# CC3000_Breakout.net
KiCad netlist of a schematic drawn in EAGLE
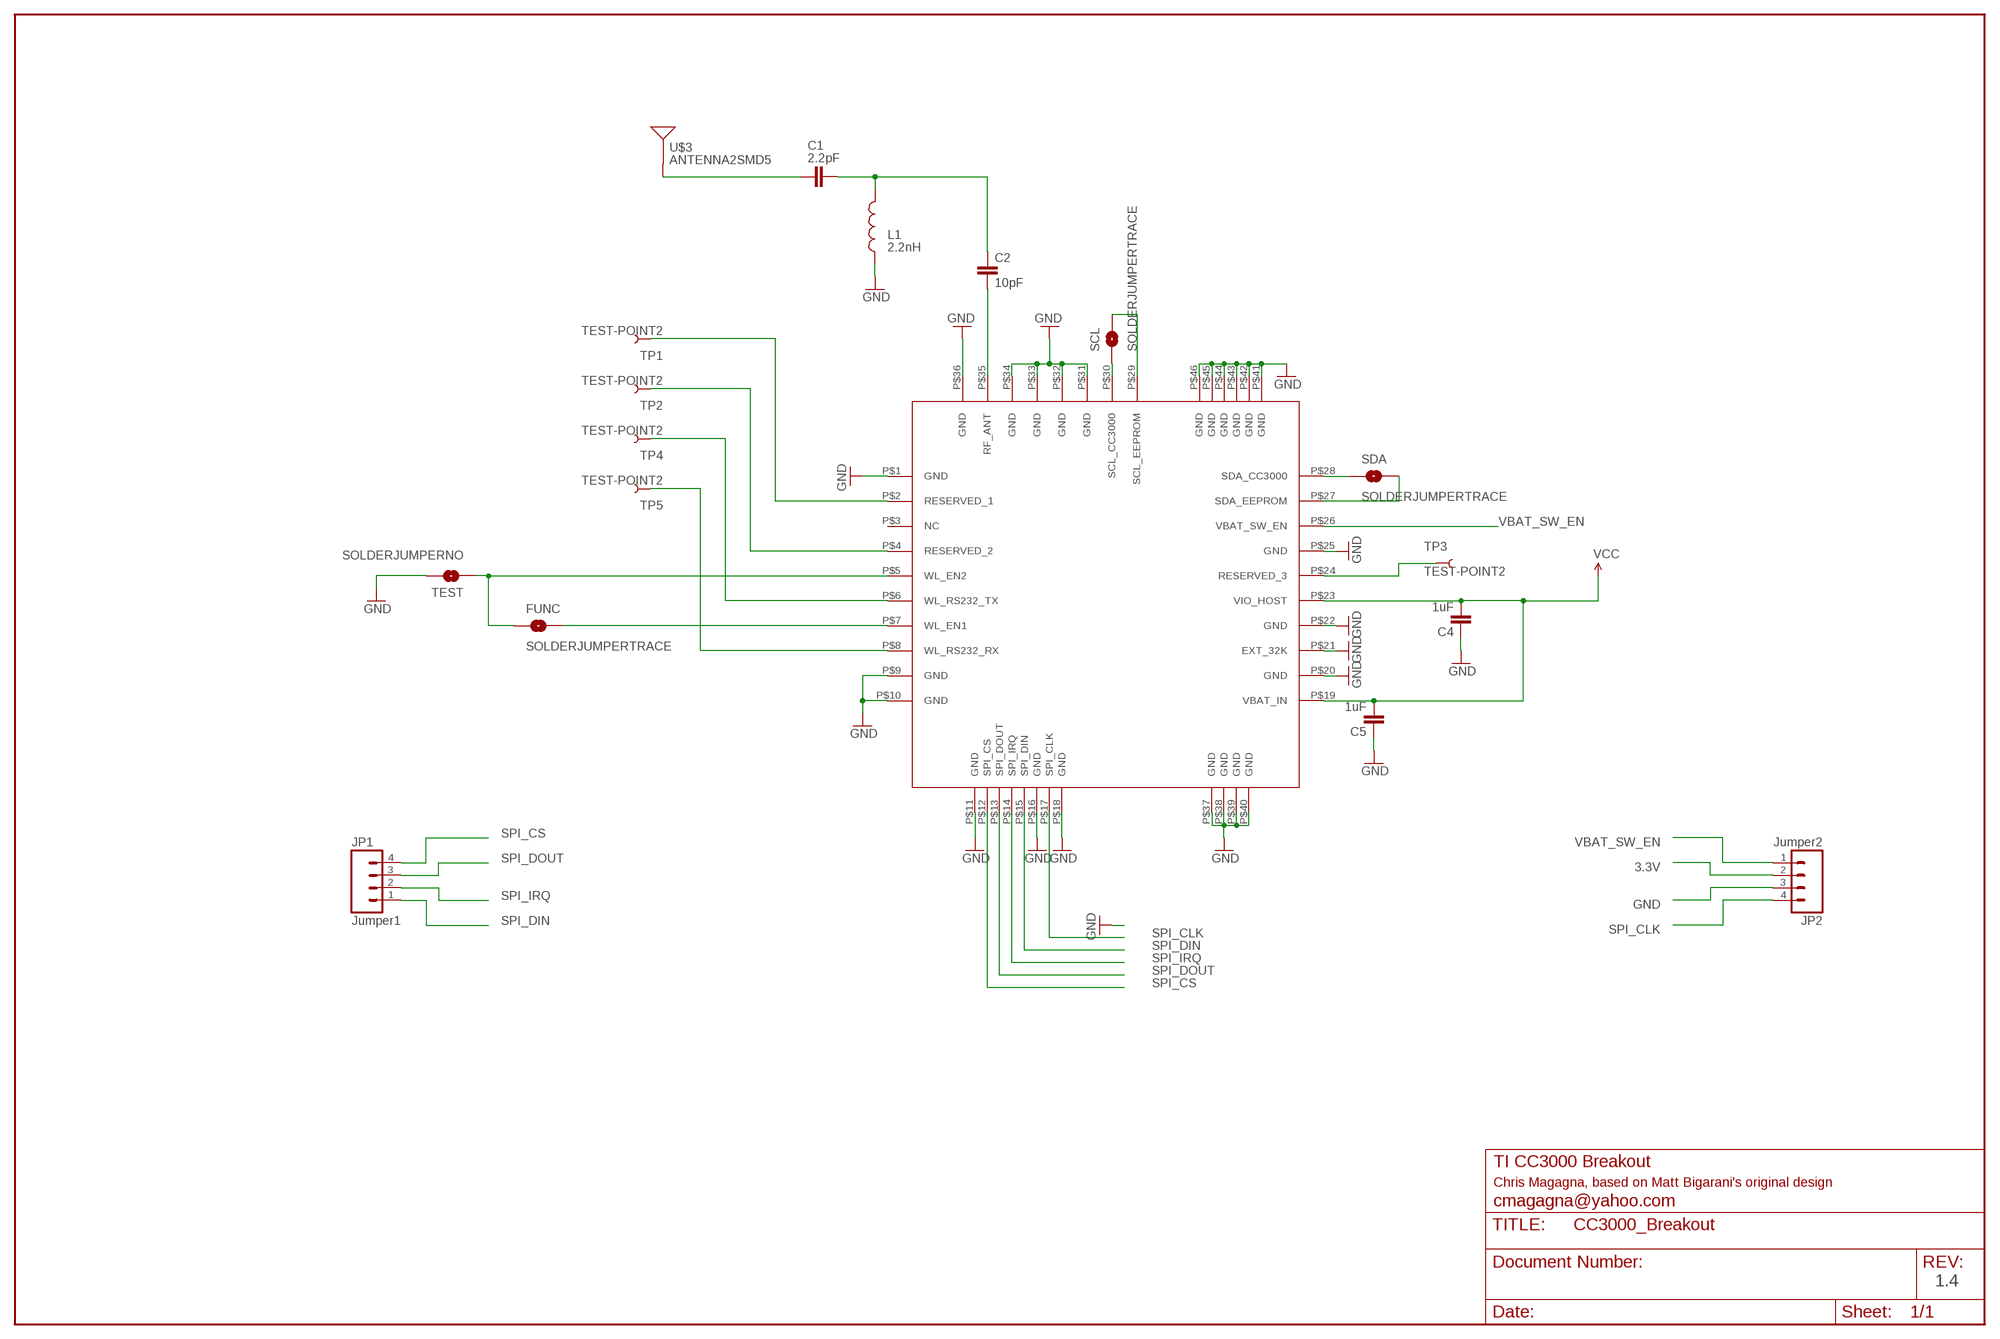
[diagram p0: schematic, sheet 1]

(export (version "E")
  (design (tool "Eeschema 10.0.6"))
  (components
    (comp (ref "C1")
      (value "2.2pF")
      (footprint "eagle-import:0402-CAP")
      (libsource (lib "eagle-import") (part "CAP0402-CAP"))
    )
    (comp (ref "C2")
      (value "10pF")
      (footprint "eagle-import:0402-CAP")
      (libsource (lib "eagle-import") (part "CAP0402-CAP"))
    )
    (comp (ref "C4")
      (value "1uF")
      (footprint "eagle-import:0402-CAP")
      (libsource (lib "eagle-import") (part "CAP0402-CAP"))
    )
    (comp (ref "C5")
      (value "1uF")
      (footprint "eagle-import:0402-CAP")
      (libsource (lib "eagle-import") (part "CAP0402-CAP"))
    )
    (comp (ref "FUNC")
      (value "SOLDERJUMPERTRACE")
      (footprint "eagle-import:SJ_2S-TRACE")
      (libsource (lib "eagle-import") (part "SparkFun-Passives_SOLDERJUMPERTRACE"))
    )
    (comp (ref "JP1")
      (value "Jumper1")
      (footprint "eagle-import:1X04")
      (libsource (lib "eagle-import") (part "M04PTH"))
    )
    (comp (ref "JP2")
      (value "Jumper2")
      (footprint "eagle-import:1X04")
      (libsource (lib "eagle-import") (part "M04PTH"))
    )
    (comp (ref "L1")
      (value "2.2nH")
      (footprint "eagle-import:C0402")
      (libsource (lib "eagle-import") (part "INDUCTOR0402"))
    )
    (comp (ref "SCL")
      (value "SOLDERJUMPERTRACE")
      (footprint "eagle-import:SJ_2S-TRACE")
      (libsource (lib "eagle-import") (part "SparkFun-Passives_SOLDERJUMPERTRACE"))
    )
    (comp (ref "SDA")
      (value "SOLDERJUMPERTRACE")
      (footprint "eagle-import:SJ_2S-TRACE")
      (libsource (lib "eagle-import") (part "SparkFun-Passives_SOLDERJUMPERTRACE"))
    )
    (comp (ref "TEST")
      (value "SOLDERJUMPERNO")
      (footprint "eagle-import:SJ_2S-NO")
      (libsource (lib "eagle-import") (part "SOLDERJUMPERNO"))
    )
    (comp (ref "TP1")
      (value "TEST-POINT2")
      (footprint "eagle-import:PAD.02X.02")
      (libsource (lib "eagle-import") (part "TEST-POINT2"))
    )
    (comp (ref "TP2")
      (value "TEST-POINT2")
      (footprint "eagle-import:PAD.02X.02")
      (libsource (lib "eagle-import") (part "TEST-POINT2"))
    )
    (comp (ref "TP3")
      (value "TEST-POINT2")
      (footprint "eagle-import:PAD.02X.02")
      (libsource (lib "eagle-import") (part "TEST-POINT2"))
    )
    (comp (ref "TP4")
      (value "TEST-POINT2")
      (footprint "eagle-import:PAD.02X.02")
      (libsource (lib "eagle-import") (part "TEST-POINT2"))
    )
    (comp (ref "TP5")
      (value "TEST-POINT2")
      (footprint "eagle-import:PAD.02X.02")
      (libsource (lib "eagle-import") (part "TEST-POINT2"))
    )
    (comp (ref "U$1")
      (value "CC3000")
      (footprint "eagle-import:CC3000")
      (fields (field (name "AUTHOR") "Matt Bigarani"))
      (libsource (lib "eagle-import") (part "CC3000"))
    )
    (comp (ref "U$3")
      (value "ANTENNA2SMD5")
      (footprint "eagle-import:ANTENNA-CHIP5")
      (libsource (lib "eagle-import") (part "ANTENNA2SMD5"))
    )
  )
  (nets
    (net (code "1") (name "/SPI_CLK") (class "Default")
      (node (ref "JP2") (pin "4") (pinfunction "4_4") (pintype "passive"))
      (node (ref "U$1") (pin "P$17") (pinfunction "SPI_CLK_P$17") (pintype "bidirectional"))
    )
    (net (code "2") (name "/SPI_CS") (class "Default")
      (node (ref "JP1") (pin "4") (pinfunction "4_4") (pintype "passive"))
      (node (ref "U$1") (pin "P$12") (pinfunction "SPI_CS_P$12") (pintype "bidirectional"))
    )
    (net (code "3") (name "/SPI_DIN") (class "Default")
      (node (ref "JP1") (pin "1") (pinfunction "1_1") (pintype "passive"))
      (node (ref "U$1") (pin "P$15") (pinfunction "SPI_DIN_P$15") (pintype "bidirectional"))
    )
    (net (code "4") (name "/SPI_DOUT") (class "Default")
      (node (ref "JP1") (pin "3") (pinfunction "3_3") (pintype "passive"))
      (node (ref "U$1") (pin "P$13") (pinfunction "SPI_DOUT_P$13") (pintype "bidirectional"))
    )
    (net (code "5") (name "/SPI_IRQ") (class "Default")
      (node (ref "JP1") (pin "2") (pinfunction "2_2") (pintype "passive"))
      (node (ref "U$1") (pin "P$14") (pinfunction "SPI_IRQ_P$14") (pintype "bidirectional"))
    )
    (net (code "6") (name "/VBAT_SW_EN") (class "Default")
      (node (ref "JP2") (pin "1") (pinfunction "1_1") (pintype "passive"))
      (node (ref "U$1") (pin "P$26") (pinfunction "VBAT_SW_EN_P$26") (pintype "bidirectional"))
    )
    (net (code "7") (name "GND") (class "Default")
      (node (ref "C4") (pin "1") (pinfunction "1_1") (pintype "passive"))
      (node (ref "C5") (pin "1") (pinfunction "1_1") (pintype "passive"))
      (node (ref "JP2") (pin "3") (pinfunction "3_3") (pintype "passive"))
      (node (ref "L1") (pin "1") (pinfunction "1_1") (pintype "passive"))
      (node (ref "TEST") (pin "2") (pinfunction "2_2") (pintype "passive"))
      (node (ref "U$1") (pin "P$1") (pinfunction "GND_P$1") (pintype "power_in"))
      (node (ref "U$1") (pin "P$10") (pinfunction "GND_P$10") (pintype "power_in"))
      (node (ref "U$1") (pin "P$11") (pinfunction "GND_P$11") (pintype "power_in"))
      (node (ref "U$1") (pin "P$16") (pinfunction "GND_P$16") (pintype "power_in"))
      (node (ref "U$1") (pin "P$18") (pinfunction "GND_P$18") (pintype "power_in"))
      (node (ref "U$1") (pin "P$20") (pinfunction "GND_P$20") (pintype "bidirectional"))
      (node (ref "U$1") (pin "P$21") (pinfunction "EXT_32K_P$21") (pintype "bidirectional"))
      (node (ref "U$1") (pin "P$22") (pinfunction "GND_P$22") (pintype "bidirectional"))
      (node (ref "U$1") (pin "P$25") (pinfunction "GND_P$25") (pintype "bidirectional"))
      (node (ref "U$1") (pin "P$31") (pinfunction "GND_P$31") (pintype "power_in"))
      (node (ref "U$1") (pin "P$32") (pinfunction "GND_P$32") (pintype "power_in"))
      (node (ref "U$1") (pin "P$33") (pinfunction "GND_P$33") (pintype "power_in"))
      (node (ref "U$1") (pin "P$34") (pinfunction "GND_P$34") (pintype "power_in"))
      (node (ref "U$1") (pin "P$36") (pinfunction "GND_P$36") (pintype "passive"))
      (node (ref "U$1") (pin "P$37") (pinfunction "GND_P$37") (pintype "power_in"))
      (node (ref "U$1") (pin "P$38") (pinfunction "GND_P$38") (pintype "passive"))
      (node (ref "U$1") (pin "P$39") (pinfunction "GND_P$39") (pintype "power_in"))
      (node (ref "U$1") (pin "P$40") (pinfunction "GND_P$40") (pintype "power_in"))
      (node (ref "U$1") (pin "P$41") (pinfunction "GND_P$41") (pintype "power_in"))
      (node (ref "U$1") (pin "P$42") (pinfunction "GND_P$42") (pintype "power_in"))
      (node (ref "U$1") (pin "P$43") (pinfunction "GND_P$43") (pintype "power_in"))
      (node (ref "U$1") (pin "P$44") (pinfunction "GND_P$44") (pintype "power_in"))
      (node (ref "U$1") (pin "P$45") (pinfunction "GND_P$45") (pintype "power_in"))
      (node (ref "U$1") (pin "P$46") (pinfunction "GND_P$46") (pintype "power_in"))
      (node (ref "U$1") (pin "P$9") (pinfunction "GND_P$9") (pintype "bidirectional"))
    )
    (net (code "8") (name "Net-(C1-Pad2)") (class "Default")
      (node (ref "C1") (pin "2") (pinfunction "2_2") (pintype "passive"))
      (node (ref "C2") (pin "1") (pinfunction "1_1") (pintype "passive"))
      (node (ref "L1") (pin "2") (pinfunction "2_2") (pintype "passive"))
    )
    (net (code "9") (name "Net-(TP1-1)") (class "Default")
      (node (ref "TP1") (pin "P$1") (pinfunction "1_P$1") (pintype "bidirectional"))
      (node (ref "U$1") (pin "P$2") (pinfunction "RESERVED_1_P$2") (pintype "bidirectional"))
    )
    (net (code "10") (name "Net-(TP2-1)") (class "Default")
      (node (ref "TP2") (pin "P$1") (pinfunction "1_P$1") (pintype "bidirectional"))
      (node (ref "U$1") (pin "P$4") (pinfunction "RESERVED_2_P$4") (pintype "bidirectional"))
    )
    (net (code "11") (name "Net-(TP3-1)") (class "Default")
      (node (ref "TP3") (pin "P$1") (pinfunction "1_P$1") (pintype "bidirectional"))
      (node (ref "U$1") (pin "P$24") (pinfunction "RESERVED_3_P$24") (pintype "bidirectional"))
    )
    (net (code "12") (name "Net-(TP4-1)") (class "Default")
      (node (ref "TP4") (pin "P$1") (pinfunction "1_P$1") (pintype "bidirectional"))
      (node (ref "U$1") (pin "P$6") (pinfunction "WL_RS232_TX_P$6") (pintype "bidirectional"))
    )
    (net (code "13") (name "Net-(TP5-1)") (class "Default")
      (node (ref "TP5") (pin "P$1") (pinfunction "1_P$1") (pintype "bidirectional"))
      (node (ref "U$1") (pin "P$8") (pinfunction "WL_RS232_RX_P$8") (pintype "bidirectional"))
    )
    (net (code "14") (name "Net-(U$1-RF_ANT)") (class "Default")
      (node (ref "C2") (pin "2") (pinfunction "2_2") (pintype "passive"))
      (node (ref "U$1") (pin "P$35") (pinfunction "RF_ANT_P$35") (pintype "bidirectional"))
    )
    (net (code "15") (name "Net-(U$1-SCL_CC3000)") (class "Default")
      (node (ref "SCL") (pin "1") (pinfunction "1_1") (pintype "passive"))
      (node (ref "U$1") (pin "P$30") (pinfunction "SCL_CC3000_P$30") (pintype "power_in"))
    )
    (net (code "16") (name "Net-(U$1-SCL_EEPROM)") (class "Default")
      (node (ref "SCL") (pin "2") (pinfunction "2_2") (pintype "passive"))
      (node (ref "U$1") (pin "P$29") (pinfunction "SCL_EEPROM_P$29") (pintype "power_in"))
    )
    (net (code "17") (name "Net-(U$1-SDA_CC3000)") (class "Default")
      (node (ref "SDA") (pin "1") (pinfunction "1_1") (pintype "passive"))
      (node (ref "U$1") (pin "P$28") (pinfunction "SDA_CC3000_P$28") (pintype "bidirectional"))
    )
    (net (code "18") (name "Net-(U$1-SDA_EEPROM)") (class "Default")
      (node (ref "SDA") (pin "2") (pinfunction "2_2") (pintype "passive"))
      (node (ref "U$1") (pin "P$27") (pinfunction "SDA_EEPROM_P$27") (pintype "bidirectional"))
    )
    (net (code "19") (name "Net-(U$1-WL_EN1)") (class "Default")
      (node (ref "FUNC") (pin "2") (pinfunction "2_2") (pintype "passive"))
      (node (ref "U$1") (pin "P$7") (pinfunction "WL_EN1_P$7") (pintype "bidirectional"))
    )
    (net (code "20") (name "Net-(U$1-WL_EN2)") (class "Default")
      (node (ref "FUNC") (pin "1") (pinfunction "1_1") (pintype "passive"))
      (node (ref "TEST") (pin "1") (pinfunction "1_1") (pintype "passive"))
      (node (ref "U$1") (pin "P$5") (pinfunction "WL_EN2_P$5") (pintype "bidirectional"))
    )
    (net (code "21") (name "Net-(U$3-SIGNAL)") (class "Default")
      (node (ref "C1") (pin "1") (pinfunction "1_1") (pintype "passive"))
      (node (ref "U$3") (pin "FEED") (pinfunction "SIGNAL_FEED") (pintype "bidirectional"))
    )
    (net (code "22") (name "VCC") (class "Default")
      (node (ref "C4") (pin "2") (pinfunction "2_2") (pintype "passive"))
      (node (ref "C5") (pin "2") (pinfunction "2_2") (pintype "passive"))
      (node (ref "JP2") (pin "2") (pinfunction "2_2") (pintype "passive"))
      (node (ref "U$1") (pin "P$19") (pinfunction "VBAT_IN_P$19") (pintype "bidirectional"))
      (node (ref "U$1") (pin "P$23") (pinfunction "VIO_HOST_P$23") (pintype "bidirectional"))
    )
    (net (code "23") (name "unconnected-(U$1-NC-PadP$3)") (class "Default")
      (node (ref "U$1") (pin "P$3") (pinfunction "NC_P$3") (pintype "no_connect"))
    )
  )
)
